# LED_Bar.net
KiCad netlist of a schematic drawn in EAGLE
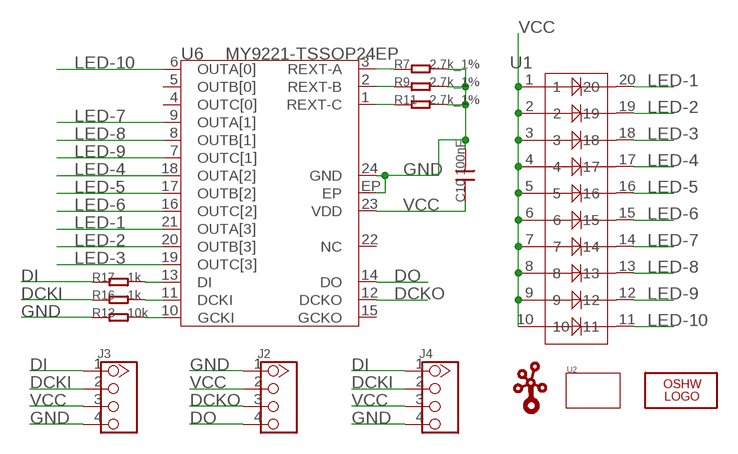
[diagram p0: schematic, sheet 1]

(export (version "E")
  (design (tool "Eeschema 10.0.6"))
  (components
    (comp (ref "C10")
      (value "100nF")
      (footprint "eagle-import:0603")
      (libsource (lib "eagle-import") (part "C-0603"))
    )
    (comp (ref "J2")
      (value "HEADER-4P-90D")
      (footprint "eagle-import:4P-2.54-90")
      (libsource (lib "eagle-import") (part "HEADER-4P-90D"))
    )
    (comp (ref "J3")
      (value "HEADER-4P'2.54-90D-FEMALE'")
      (footprint "eagle-import:4P-2.54-90D-FEMALE")
      (libsource (lib "eagle-import") (part "HEADER-4P'2.54-90D-FEMALE'"))
    )
    (comp (ref "J4")
      (value "TWIG-4P-2.0-2.0")
      (footprint "eagle-import:4P-2.0")
      (libsource (lib "eagle-import") (part "TWIG-4P-2.0-2.0"))
    )
    (comp (ref "LOGO1")
      (value "LOGO-OSHW-FILLX0150-NT")
      (footprint "eagle-import:OSHW_FILLX150_NOTEXT")
      (libsource (lib "eagle-import") (part "LOGO-OSHW-FILLX0150-NT"))
    )
    (comp (ref "R7")
      (value "2.7k_1%")
      (footprint "eagle-import:0603")
      (libsource (lib "eagle-import") (part "R-0603"))
    )
    (comp (ref "R9")
      (value "2.7k_1%")
      (footprint "eagle-import:0603")
      (libsource (lib "eagle-import") (part "R-0603"))
    )
    (comp (ref "R11")
      (value "2.7k_1%")
      (footprint "eagle-import:0603")
      (libsource (lib "eagle-import") (part "R-0603"))
    )
    (comp (ref "R13")
      (value "10k")
      (footprint "eagle-import:0603")
      (libsource (lib "eagle-import") (part "R-0603"))
    )
    (comp (ref "R16")
      (value "1k")
      (footprint "eagle-import:0603")
      (libsource (lib "eagle-import") (part "R-0603"))
    )
    (comp (ref "R17")
      (value "1k")
      (footprint "eagle-import:0603")
      (libsource (lib "eagle-import") (part "R-0603"))
    )
    (comp (ref "U$1")
      (value "LOGO-TWIGTWIGLOGO_SMALL")
      (footprint "eagle-import:TWIGLOGO_SMALL")
      (libsource (lib "eagle-import") (part "LOGO-TWIGTWIGLOGO_SMALL"))
    )
    (comp (ref "U1")
      (value "LED-20P")
      (footprint "eagle-import:20P-DIP-2.54-25.5X10.1X8.4H")
      (libsource (lib "eagle-import") (part "LED-20P"))
    )
    (comp (ref "U2")
      (value "TWIG-2U")
      (footprint "eagle-import:2U-DIM-W_-DRILL")
      (libsource (lib "eagle-import") (part "TWIG-2U"))
    )
    (comp (ref "U6")
      (value "MY9221-TSSOP24EP")
      (footprint "eagle-import:TSSOP24EP")
      (libsource (lib "eagle-import") (part "MY9221-TSSOP24EP"))
    )
  )
  (nets
    (net (code "1") (name "/DCKI") (class "Default")
      (node (ref "J3") (pin "2") (pinfunction "P$2_2") (pintype "bidirectional"))
      (node (ref "J4") (pin "2") (pinfunction "2_2") (pintype "bidirectional"))
      (node (ref "R16") (pin "1") (pinfunction "1_1") (pintype "passive"))
    )
    (net (code "2") (name "/DCKO") (class "Default")
      (node (ref "J2") (pin "3") (pinfunction "P$3_3") (pintype "bidirectional"))
      (node (ref "U6") (pin "12") (pinfunction "DCKO_12") (pintype "bidirectional"))
    )
    (net (code "3") (name "/DI") (class "Default")
      (node (ref "J3") (pin "1") (pinfunction "P$1_1") (pintype "bidirectional"))
      (node (ref "J4") (pin "1") (pinfunction "1_1") (pintype "bidirectional"))
      (node (ref "R17") (pin "1") (pinfunction "1_1") (pintype "passive"))
    )
    (net (code "4") (name "/DO") (class "Default")
      (node (ref "J2") (pin "4") (pinfunction "P$4_4") (pintype "bidirectional"))
      (node (ref "U6") (pin "14") (pinfunction "DO_14") (pintype "bidirectional"))
    )
    (net (code "5") (name "/GND") (class "Default")
      (node (ref "C10") (pin "2") (pinfunction "2_2") (pintype "passive"))
      (node (ref "J2") (pin "1") (pinfunction "P$1_1") (pintype "bidirectional"))
      (node (ref "J3") (pin "4") (pinfunction "P$4_4") (pintype "bidirectional"))
      (node (ref "J4") (pin "4") (pinfunction "4_4") (pintype "bidirectional"))
      (node (ref "R11") (pin "2") (pinfunction "2_2") (pintype "passive"))
      (node (ref "R13") (pin "1") (pinfunction "1_1") (pintype "passive"))
      (node (ref "R7") (pin "2") (pinfunction "2_2") (pintype "passive"))
      (node (ref "R9") (pin "2") (pinfunction "2_2") (pintype "passive"))
      (node (ref "U6") (pin "24") (pinfunction "GND_24") (pintype "power_in"))
      (node (ref "U6") (pin "EP") (pinfunction "EP_EP") (pintype "bidirectional"))
    )
    (net (code "6") (name "/LED-1") (class "Default")
      (node (ref "U1") (pin "20") (pinfunction "20_20") (pintype "bidirectional"))
      (node (ref "U6") (pin "21") (pinfunction "OUTA[3]_21") (pintype "bidirectional"))
    )
    (net (code "7") (name "/LED-2") (class "Default")
      (node (ref "U1") (pin "19") (pinfunction "19_19") (pintype "bidirectional"))
      (node (ref "U6") (pin "20") (pinfunction "OUTB[3]_20") (pintype "bidirectional"))
    )
    (net (code "8") (name "/LED-3") (class "Default")
      (node (ref "U1") (pin "18") (pinfunction "18_18") (pintype "bidirectional"))
      (node (ref "U6") (pin "19") (pinfunction "OUTC[3]_19") (pintype "bidirectional"))
    )
    (net (code "9") (name "/LED-4") (class "Default")
      (node (ref "U1") (pin "17") (pinfunction "17_17") (pintype "bidirectional"))
      (node (ref "U6") (pin "18") (pinfunction "OUTA[2]_18") (pintype "bidirectional"))
    )
    (net (code "10") (name "/LED-5") (class "Default")
      (node (ref "U1") (pin "16") (pinfunction "16_16") (pintype "bidirectional"))
      (node (ref "U6") (pin "17") (pinfunction "OUTB[2]_17") (pintype "bidirectional"))
    )
    (net (code "11") (name "/LED-6") (class "Default")
      (node (ref "U1") (pin "15") (pinfunction "15_15") (pintype "bidirectional"))
      (node (ref "U6") (pin "16") (pinfunction "OUTC[2]_16") (pintype "bidirectional"))
    )
    (net (code "12") (name "/LED-7") (class "Default")
      (node (ref "U1") (pin "14") (pinfunction "14_14") (pintype "bidirectional"))
      (node (ref "U6") (pin "9") (pinfunction "OUTA[1]_9") (pintype "bidirectional"))
    )
    (net (code "13") (name "/LED-8") (class "Default")
      (node (ref "U1") (pin "13") (pinfunction "13_13") (pintype "bidirectional"))
      (node (ref "U6") (pin "8") (pinfunction "OUTB[1]_8") (pintype "bidirectional"))
    )
    (net (code "14") (name "/LED-9") (class "Default")
      (node (ref "U1") (pin "12") (pinfunction "12_12") (pintype "bidirectional"))
      (node (ref "U6") (pin "7") (pinfunction "OUTC[1]_7") (pintype "bidirectional"))
    )
    (net (code "15") (name "/LED-10") (class "Default")
      (node (ref "U1") (pin "11") (pinfunction "11_11") (pintype "bidirectional"))
      (node (ref "U6") (pin "6") (pinfunction "OUTA[0]_6") (pintype "bidirectional"))
    )
    (net (code "16") (name "/VCC") (class "Default")
      (node (ref "C10") (pin "1") (pinfunction "1_1") (pintype "passive"))
      (node (ref "J2") (pin "2") (pinfunction "P$2_2") (pintype "bidirectional"))
      (node (ref "J3") (pin "3") (pinfunction "P$3_3") (pintype "bidirectional"))
      (node (ref "J4") (pin "3") (pinfunction "3_3") (pintype "bidirectional"))
      (node (ref "U1") (pin "1") (pinfunction "1_1") (pintype "bidirectional"))
      (node (ref "U1") (pin "10") (pinfunction "10_10") (pintype "bidirectional"))
      (node (ref "U1") (pin "2") (pinfunction "2_2") (pintype "bidirectional"))
      (node (ref "U1") (pin "3") (pinfunction "3_3") (pintype "bidirectional"))
      (node (ref "U1") (pin "4") (pinfunction "4_4") (pintype "bidirectional"))
      (node (ref "U1") (pin "5") (pinfunction "5_5") (pintype "bidirectional"))
      (node (ref "U1") (pin "6") (pinfunction "6_6") (pintype "bidirectional"))
      (node (ref "U1") (pin "7") (pinfunction "7_7") (pintype "bidirectional"))
      (node (ref "U1") (pin "8") (pinfunction "8_8") (pintype "bidirectional"))
      (node (ref "U1") (pin "9") (pinfunction "9_9") (pintype "bidirectional"))
      (node (ref "U6") (pin "23") (pinfunction "VDD_23") (pintype "power_in"))
    )
    (net (code "17") (name "Net-(U6-DCKI)") (class "Default")
      (node (ref "R16") (pin "2") (pinfunction "2_2") (pintype "passive"))
      (node (ref "U6") (pin "11") (pinfunction "DCKI_11") (pintype "bidirectional"))
    )
    (net (code "18") (name "Net-(U6-DI)") (class "Default")
      (node (ref "R17") (pin "2") (pinfunction "2_2") (pintype "passive"))
      (node (ref "U6") (pin "13") (pinfunction "DI_13") (pintype "bidirectional"))
    )
    (net (code "19") (name "Net-(U6-GCKI)") (class "Default")
      (node (ref "R13") (pin "2") (pinfunction "2_2") (pintype "passive"))
      (node (ref "U6") (pin "10") (pinfunction "GCKI_10") (pintype "bidirectional"))
    )
    (net (code "20") (name "Net-(U6-REXT-A)") (class "Default")
      (node (ref "R7") (pin "1") (pinfunction "1_1") (pintype "passive"))
      (node (ref "U6") (pin "3") (pinfunction "REXT-A_3") (pintype "bidirectional"))
    )
    (net (code "21") (name "Net-(U6-REXT-B)") (class "Default")
      (node (ref "R9") (pin "1") (pinfunction "1_1") (pintype "passive"))
      (node (ref "U6") (pin "2") (pinfunction "REXT-B_2") (pintype "bidirectional"))
    )
    (net (code "22") (name "Net-(U6-REXT-C)") (class "Default")
      (node (ref "R11") (pin "1") (pinfunction "1_1") (pintype "passive"))
      (node (ref "U6") (pin "1") (pinfunction "REXT-C_1") (pintype "bidirectional"))
    )
    (net (code "23") (name "unconnected-(U6-GCKO-Pad15)") (class "Default")
      (node (ref "U6") (pin "15") (pinfunction "GCKO_15") (pintype "bidirectional"))
    )
    (net (code "24") (name "unconnected-(U6-NC-Pad22)") (class "Default")
      (node (ref "U6") (pin "22") (pinfunction "NC_22") (pintype "bidirectional"))
    )
    (net (code "25") (name "unconnected-(U6-OUTB[0]-Pad5)") (class "Default")
      (node (ref "U6") (pin "5") (pinfunction "OUTB[0]_5") (pintype "bidirectional"))
    )
    (net (code "26") (name "unconnected-(U6-OUTC[0]-Pad4)") (class "Default")
      (node (ref "U6") (pin "4") (pinfunction "OUTC[0]_4") (pintype "bidirectional"))
    )
  )
)
